# Adafruit_CC3000_Breakout.net
KiCad netlist of a schematic drawn in EAGLE
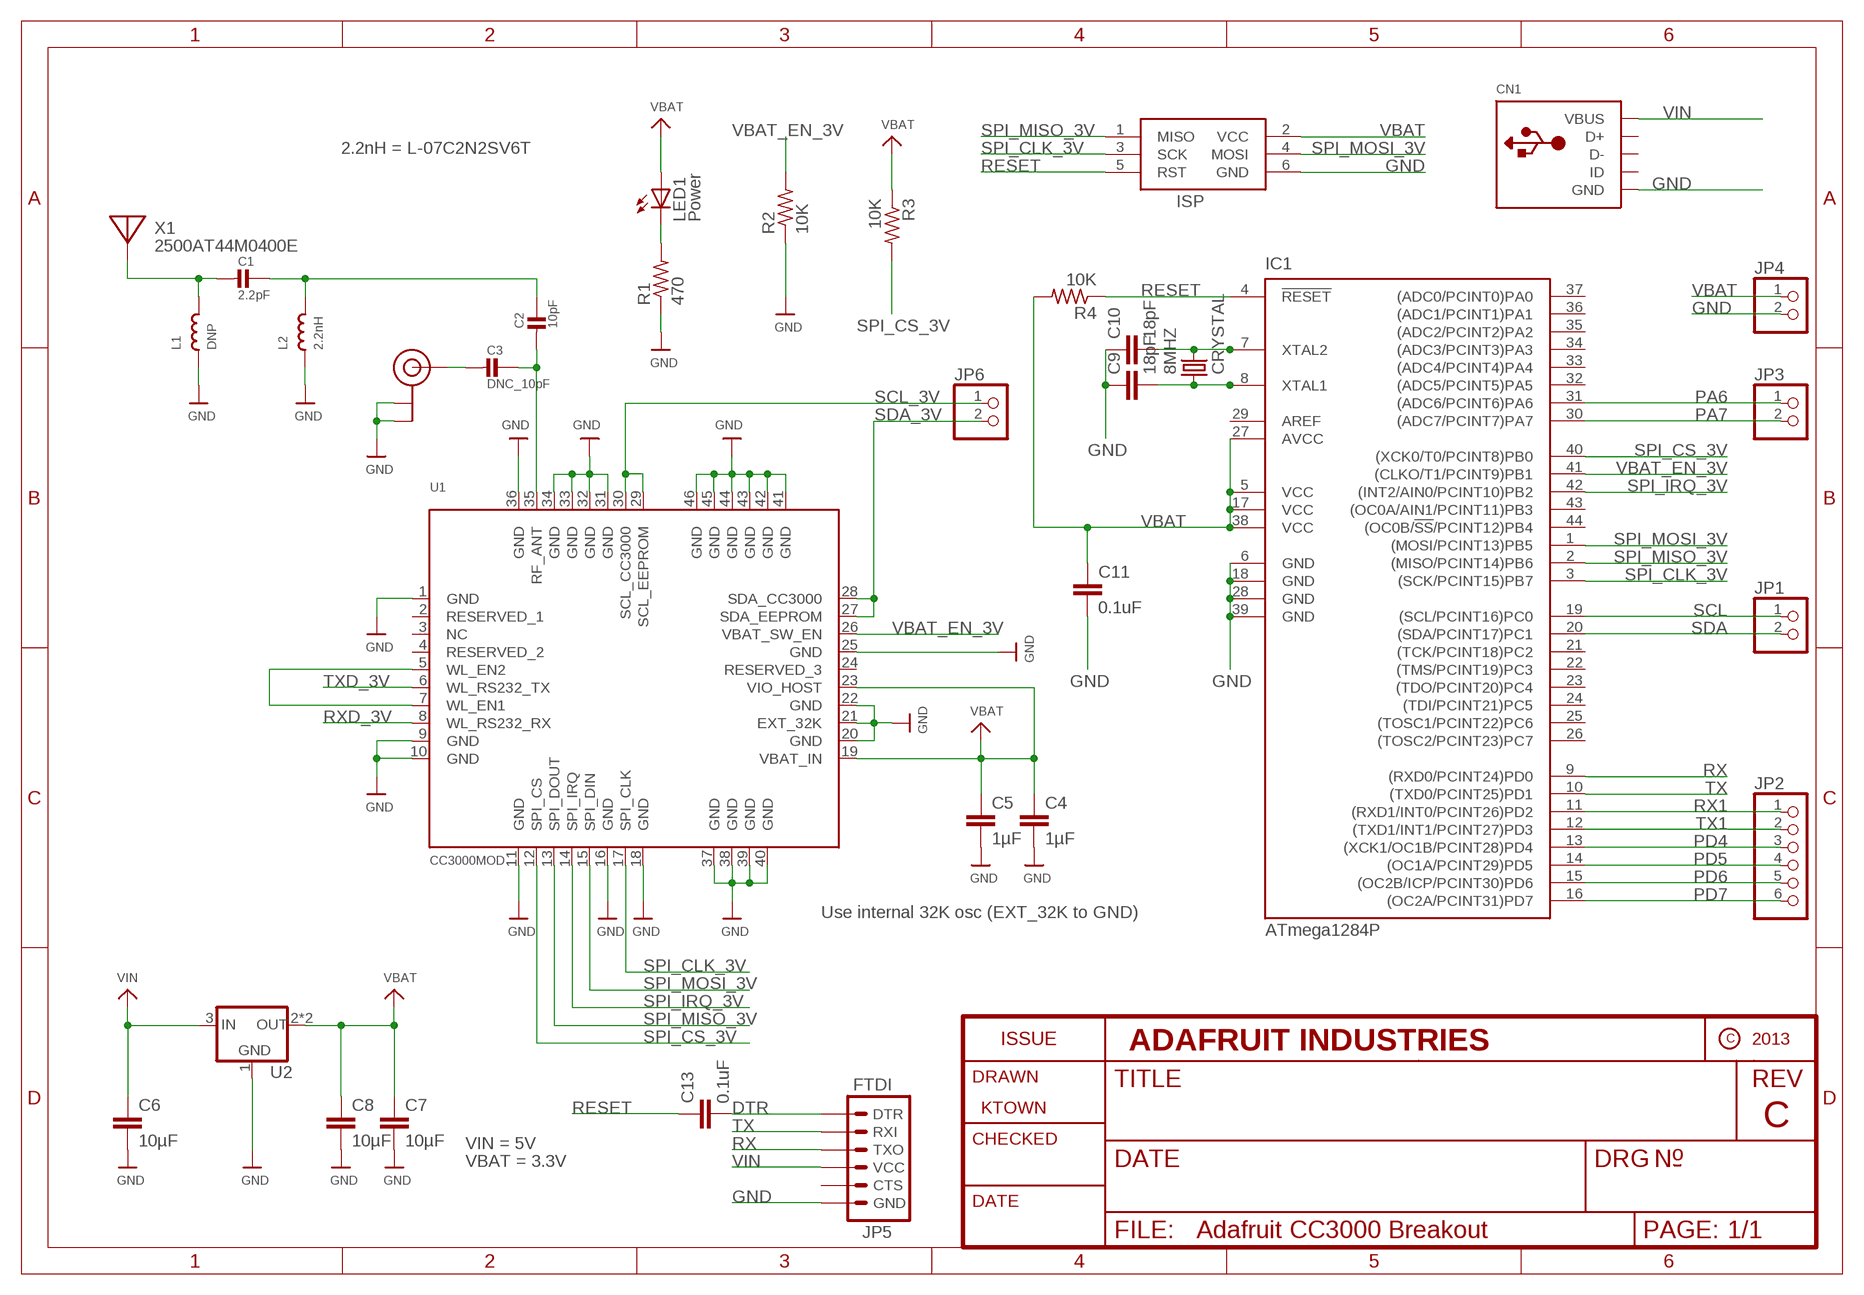
[diagram p0: schematic, sheet 1]

(export (version "E")
  (design (tool "Eeschema 10.0.6"))
  (components
    (comp (ref "8MHZ")
      (value "CRYSTAL")
      (footprint "eagle-import:2-SMD-5X3MM")
      (libsource (lib "eagle-import") (part "CRYSTAL"))
    )
    (comp (ref "C1")
      (value "2.2pF")
      (footprint "eagle-import:_0402")
      (libsource (lib "eagle-import") (part "CAP_CERAMIC_0402"))
    )
    (comp (ref "C2")
      (value "10pF")
      (footprint "eagle-import:_0402")
      (libsource (lib "eagle-import") (part "CAP_CERAMIC_0402"))
    )
    (comp (ref "C3")
      (value "DNC_10pF")
      (footprint "eagle-import:_0402")
      (libsource (lib "eagle-import") (part "CAP_CERAMIC_0402"))
    )
    (comp (ref "C4")
      (value "1µF")
      (footprint "eagle-import:C1206")
      (libsource (lib "eagle-import") (part "C-EUC1206"))
    )
    (comp (ref "C5")
      (value "1µF")
      (footprint "eagle-import:C1206")
      (libsource (lib "eagle-import") (part "C-EUC1206"))
    )
    (comp (ref "C6")
      (value "10µF")
      (footprint "eagle-import:C1206")
      (libsource (lib "eagle-import") (part "C-EUC1206"))
    )
    (comp (ref "C7")
      (value "10µF")
      (footprint "eagle-import:C1206")
      (libsource (lib "eagle-import") (part "C-EUC1206"))
    )
    (comp (ref "C8")
      (value "10µF")
      (footprint "eagle-import:C1206")
      (libsource (lib "eagle-import") (part "C-EUC1206"))
    )
    (comp (ref "C9")
      (value "18pF")
      (footprint "eagle-import:C1206")
      (libsource (lib "eagle-import") (part "C-EUC1206"))
    )
    (comp (ref "C10")
      (value "18pF")
      (footprint "eagle-import:C1206")
      (libsource (lib "eagle-import") (part "C-EUC1206"))
    )
    (comp (ref "C11")
      (value "0.1uF")
      (footprint "eagle-import:C1206")
      (libsource (lib "eagle-import") (part "C-EUC1206"))
    )
    (comp (ref "C13")
      (value "0.1uF")
      (footprint "eagle-import:C1206")
      (libsource (lib "eagle-import") (part "C-EUC1206"))
    )
    (comp (ref "CN1")
      (value "USBPWR")
      (footprint "eagle-import:USB-MINIB-POWER")
      (libsource (lib "eagle-import") (part "USBPWR"))
    )
    (comp (ref "IC1")
      (value "ATmega1284P")
      (footprint "eagle-import:TQFP44")
      (libsource (lib "eagle-import") (part "MEGA164P/324P/644P-AU"))
    )
    (comp (ref "ISP")
      (value "AVRISP-6")
      (footprint "eagle-import:AVRISP")
      (libsource (lib "eagle-import") (part "AVRISP-6"))
    )
    (comp (ref "JP1")
      (value "PINHD-1X2")
      (footprint "eagle-import:1X02")
      (libsource (lib "eagle-import") (part "PINHD-1X2"))
    )
    (comp (ref "JP2")
      (value "PINHD-1X6")
      (footprint "eagle-import:1X06")
      (libsource (lib "eagle-import") (part "PINHD-1X6"))
    )
    (comp (ref "JP3")
      (value "PINHD-1X2")
      (footprint "eagle-import:1X02")
      (libsource (lib "eagle-import") (part "PINHD-1X2"))
    )
    (comp (ref "JP4")
      (value "PINHD-1X2")
      (footprint "eagle-import:1X02")
      (libsource (lib "eagle-import") (part "PINHD-1X2"))
    )
    (comp (ref "JP5")
      (value "FTDI")
      (footprint "eagle-import:1X06")
      (libsource (lib "eagle-import") (part "ARDUINO_SERIAL_PROGRAMPTH"))
    )
    (comp (ref "JP6")
      (value "PINHD-1X2")
      (footprint "eagle-import:1X02")
      (libsource (lib "eagle-import") (part "PINHD-1X2"))
    )
    (comp (ref "L1")
      (value "DNP")
      (footprint "eagle-import:_0402")
      (libsource (lib "eagle-import") (part "INDUCTOR_0402"))
    )
    (comp (ref "L2")
      (value "2.2nH")
      (footprint "eagle-import:_0402")
      (libsource (lib "eagle-import") (part "INDUCTOR_0402"))
    )
    (comp (ref "LED1")
      (value "Power")
      (footprint "eagle-import:1206")
      (libsource (lib "eagle-import") (part "LEDSMT1206"))
    )
    (comp (ref "R1")
      (value "470")
      (footprint "eagle-import:R1206")
      (libsource (lib "eagle-import") (part "R-US_R1206"))
    )
    (comp (ref "R2")
      (value "10K")
      (footprint "eagle-import:R1206")
      (libsource (lib "eagle-import") (part "R-US_R1206"))
    )
    (comp (ref "R3")
      (value "10K")
      (footprint "eagle-import:R1206")
      (libsource (lib "eagle-import") (part "R-US_R1206"))
    )
    (comp (ref "R4")
      (value "10K")
      (footprint "eagle-import:R1206")
      (libsource (lib "eagle-import") (part "R-US_R1206"))
    )
    (comp (ref "U$35")
      (value "U.FL")
      (footprint "eagle-import:U.FL")
      (libsource (lib "eagle-import") (part "U.FL"))
    )
    (comp (ref "U1")
      (value "CC3000MOD")
      (footprint "eagle-import:CC3000MOD")
      (libsource (lib "eagle-import") (part "CC3000MOD"))
    )
    (comp (ref "U2")
      (value "VREG_SOT223")
      (footprint "eagle-import:SOT223-R")
      (libsource (lib "eagle-import") (part "VREG_SOT223"))
    )
    (comp (ref "X1")
      (value "2500AT44M0400E")
      (footprint "eagle-import:ANT_2500AT44M0400")
      (libsource (lib "eagle-import") (part "ANTENNA_JOHANSON_2500AT44M0400"))
    )
  )
  (nets
    (net (code "1") (name "/AREF") (class "Default")
      (node (ref "IC1") (pin "29") (pinfunction "AREF_29") (pintype "power_in"))
    )
    (net (code "2") (name "/DTR") (class "Default")
      (node (ref "C13") (pin "2") (pinfunction "2_2") (pintype "passive"))
      (node (ref "JP5") (pin "DTR") (pinfunction "DTR_DTR") (pintype "passive"))
    )
    (net (code "3") (name "/PA6") (class "Default")
      (node (ref "IC1") (pin "31") (pinfunction "(ADC6/PCINT6)PA6_31") (pintype "bidirectional"))
      (node (ref "JP3") (pin "1") (pinfunction "1_1") (pintype "passive"))
    )
    (net (code "4") (name "/PA7") (class "Default")
      (node (ref "IC1") (pin "30") (pinfunction "(ADC7/PCINT7)PA7_30") (pintype "bidirectional"))
      (node (ref "JP3") (pin "2") (pinfunction "2_2") (pintype "passive"))
    )
    (net (code "5") (name "/PD4") (class "Default")
      (node (ref "IC1") (pin "13") (pinfunction "(XCK1/OC1B/PCINT28)PD4_13") (pintype "bidirectional"))
      (node (ref "JP2") (pin "3") (pinfunction "3_3") (pintype "passive"))
    )
    (net (code "6") (name "/PD5") (class "Default")
      (node (ref "IC1") (pin "14") (pinfunction "(OC1A/PCINT29)PD5_14") (pintype "bidirectional"))
      (node (ref "JP2") (pin "4") (pinfunction "4_4") (pintype "passive"))
    )
    (net (code "7") (name "/PD6") (class "Default")
      (node (ref "IC1") (pin "15") (pinfunction "(OC2B/ICP/PCINT30)PD6_15") (pintype "bidirectional"))
      (node (ref "JP2") (pin "5") (pinfunction "5_5") (pintype "passive"))
    )
    (net (code "8") (name "/PD7") (class "Default")
      (node (ref "IC1") (pin "16") (pinfunction "(OC2A/PCINT31)PD7_16") (pintype "bidirectional"))
      (node (ref "JP2") (pin "6") (pinfunction "6_6") (pintype "passive"))
    )
    (net (code "9") (name "/RESET") (class "Default")
      (node (ref "C13") (pin "1") (pinfunction "1_1") (pintype "passive"))
      (node (ref "IC1") (pin "4") (pinfunction "~{RESET}_4") (pintype "input"))
      (node (ref "ISP") (pin "5") (pinfunction "RST_5") (pintype "output"))
      (node (ref "R4") (pin "1") (pinfunction "1_1") (pintype "passive"))
    )
    (net (code "10") (name "/RX") (class "Default")
      (node (ref "IC1") (pin "9") (pinfunction "(RXD0/PCINT24)PD0_9") (pintype "bidirectional"))
      (node (ref "JP5") (pin "TXO") (pinfunction "TXO_TXO") (pintype "passive"))
    )
    (net (code "11") (name "/RX1") (class "Default")
      (node (ref "IC1") (pin "11") (pinfunction "(RXD1/INT0/PCINT26)PD2_11") (pintype "bidirectional"))
      (node (ref "JP2") (pin "1") (pinfunction "1_1") (pintype "passive"))
    )
    (net (code "12") (name "/RXD_3V") (class "Default")
      (node (ref "U1") (pin "8") (pinfunction "WL_RS232_RX_8") (pintype "input"))
    )
    (net (code "13") (name "/SCL") (class "Default")
      (node (ref "IC1") (pin "19") (pinfunction "(SCL/PCINT16)PC0_19") (pintype "bidirectional"))
      (node (ref "JP1") (pin "1") (pinfunction "1_1") (pintype "passive"))
    )
    (net (code "14") (name "/SCL_3V") (class "Default")
      (node (ref "JP6") (pin "1") (pinfunction "1_1") (pintype "passive"))
      (node (ref "U1") (pin "29") (pinfunction "SCL_EEPROM_29") (pintype "bidirectional"))
      (node (ref "U1") (pin "30") (pinfunction "SCL_CC3000_30") (pintype "bidirectional"))
    )
    (net (code "15") (name "/SDA") (class "Default")
      (node (ref "IC1") (pin "20") (pinfunction "(SDA/PCINT17)PC1_20") (pintype "bidirectional"))
      (node (ref "JP1") (pin "2") (pinfunction "2_2") (pintype "passive"))
    )
    (net (code "16") (name "/SDA_3V") (class "Default")
      (node (ref "JP6") (pin "2") (pinfunction "2_2") (pintype "passive"))
      (node (ref "U1") (pin "27") (pinfunction "SDA_EEPROM_27") (pintype "bidirectional"))
      (node (ref "U1") (pin "28") (pinfunction "SDA_CC3000_28") (pintype "bidirectional"))
    )
    (net (code "17") (name "/SPI_CLK_3V") (class "Default")
      (node (ref "IC1") (pin "3") (pinfunction "(SCK/PCINT15)PB7_3") (pintype "bidirectional"))
      (node (ref "ISP") (pin "3") (pinfunction "SCK_3") (pintype "output"))
      (node (ref "U1") (pin "17") (pinfunction "SPI_CLK_17") (pintype "input"))
    )
    (net (code "18") (name "/SPI_CS_3V") (class "Default")
      (node (ref "IC1") (pin "40") (pinfunction "(XCK0/T0/PCINT8)PB0_40") (pintype "bidirectional"))
      (node (ref "R3") (pin "2") (pinfunction "2_2") (pintype "passive"))
      (node (ref "U1") (pin "12") (pinfunction "SPI_CS_12") (pintype "input"))
    )
    (net (code "19") (name "/SPI_IRQ_3V") (class "Default")
      (node (ref "IC1") (pin "42") (pinfunction "(INT2/AIN0/PCINT10)PB2_42") (pintype "bidirectional"))
      (node (ref "U1") (pin "14") (pinfunction "SPI_IRQ_14") (pintype "output"))
    )
    (net (code "20") (name "/SPI_MISO_3V") (class "Default")
      (node (ref "IC1") (pin "2") (pinfunction "(MISO/PCINT14)PB6_2") (pintype "bidirectional"))
      (node (ref "ISP") (pin "1") (pinfunction "MISO_1") (pintype "input"))
      (node (ref "U1") (pin "13") (pinfunction "SPI_DOUT_13") (pintype "output"))
    )
    (net (code "21") (name "/SPI_MOSI_3V") (class "Default")
      (node (ref "IC1") (pin "1") (pinfunction "(MOSI/PCINT13)PB5_1") (pintype "bidirectional"))
      (node (ref "ISP") (pin "4") (pinfunction "MOSI_4") (pintype "output"))
      (node (ref "U1") (pin "15") (pinfunction "SPI_DIN_15") (pintype "input"))
    )
    (net (code "22") (name "/TX") (class "Default")
      (node (ref "IC1") (pin "10") (pinfunction "(TXD0/PCINT25)PD1_10") (pintype "bidirectional"))
      (node (ref "JP5") (pin "RXI") (pinfunction "RXI_RXI") (pintype "passive"))
    )
    (net (code "23") (name "/TX1") (class "Default")
      (node (ref "IC1") (pin "12") (pinfunction "(TXD1/INT1/PCINT27)PD3_12") (pintype "bidirectional"))
      (node (ref "JP2") (pin "2") (pinfunction "2_2") (pintype "passive"))
    )
    (net (code "24") (name "/TXD_3V") (class "Default")
      (node (ref "U1") (pin "6") (pinfunction "WL_RS232_TX_6") (pintype "output"))
    )
    (net (code "25") (name "/VBAT_EN_3V") (class "Default")
      (node (ref "IC1") (pin "41") (pinfunction "(CLKO/T1/PCINT9)PB1_41") (pintype "bidirectional"))
      (node (ref "R2") (pin "2") (pinfunction "2_2") (pintype "passive"))
      (node (ref "U1") (pin "26") (pinfunction "VBAT_SW_EN_26") (pintype "input"))
    )
    (net (code "26") (name "GND") (class "Default")
      (node (ref "C10") (pin "1") (pinfunction "1_1") (pintype "passive"))
      (node (ref "C11") (pin "2") (pinfunction "2_2") (pintype "passive"))
      (node (ref "C4") (pin "2") (pinfunction "2_2") (pintype "passive"))
      (node (ref "C5") (pin "2") (pinfunction "2_2") (pintype "passive"))
      (node (ref "C6") (pin "2") (pinfunction "2_2") (pintype "passive"))
      (node (ref "C7") (pin "2") (pinfunction "2_2") (pintype "passive"))
      (node (ref "C8") (pin "2") (pinfunction "2_2") (pintype "passive"))
      (node (ref "C9") (pin "1") (pinfunction "1_1") (pintype "passive"))
      (node (ref "CN1") (pin "GND") (pinfunction "GND_GND") (pintype "power_in"))
      (node (ref "IC1") (pin "18") (pinfunction "GND_18") (pintype "power_in"))
      (node (ref "IC1") (pin "28") (pinfunction "GND_28") (pintype "power_in"))
      (node (ref "IC1") (pin "39") (pinfunction "GND_39") (pintype "power_in"))
      (node (ref "IC1") (pin "6") (pinfunction "GND_6") (pintype "power_in"))
      (node (ref "ISP") (pin "6") (pinfunction "GND_6") (pintype "power_in"))
      (node (ref "JP4") (pin "2") (pinfunction "2_2") (pintype "passive"))
      (node (ref "JP5") (pin "GND") (pinfunction "GND_GND") (pintype "passive"))
      (node (ref "L1") (pin "1") (pinfunction "1_1") (pintype "passive"))
      (node (ref "L2") (pin "1") (pinfunction "1_1") (pintype "passive"))
      (node (ref "R1") (pin "1") (pinfunction "1_1") (pintype "passive"))
      (node (ref "R2") (pin "1") (pinfunction "1_1") (pintype "passive"))
      (node (ref "U$35") (pin "P$1") (pinfunction "GND_P$1") (pintype "bidirectional"))
      (node (ref "U$35") (pin "P$2") (pinfunction "GND_P$2") (pintype "bidirectional"))
      (node (ref "U1") (pin "1") (pinfunction "GND_1") (pintype "power_in"))
      (node (ref "U1") (pin "10") (pinfunction "GND_10") (pintype "power_in"))
      (node (ref "U1") (pin "11") (pinfunction "GND_11") (pintype "power_in"))
      (node (ref "U1") (pin "16") (pinfunction "GND_16") (pintype "power_in"))
      (node (ref "U1") (pin "18") (pinfunction "GND_18") (pintype "power_in"))
      (node (ref "U1") (pin "20") (pinfunction "GND_20") (pintype "power_in"))
      (node (ref "U1") (pin "21") (pinfunction "EXT_32K_21") (pintype "bidirectional"))
      (node (ref "U1") (pin "22") (pinfunction "GND_22") (pintype "power_in"))
      (node (ref "U1") (pin "25") (pinfunction "GND_25") (pintype "power_in"))
      (node (ref "U1") (pin "31") (pinfunction "GND_31") (pintype "power_in"))
      (node (ref "U1") (pin "32") (pinfunction "GND_32") (pintype "power_in"))
      (node (ref "U1") (pin "33") (pinfunction "GND_33") (pintype "power_in"))
      (node (ref "U1") (pin "34") (pinfunction "GND_34") (pintype "power_in"))
      (node (ref "U1") (pin "36") (pinfunction "GND_36") (pintype "power_in"))
      (node (ref "U1") (pin "37") (pinfunction "GND_37") (pintype "power_in"))
      (node (ref "U1") (pin "38") (pinfunction "GND_38") (pintype "power_in"))
      (node (ref "U1") (pin "39") (pinfunction "GND_39") (pintype "power_in"))
      (node (ref "U1") (pin "40") (pinfunction "GND_40") (pintype "power_in"))
      (node (ref "U1") (pin "41") (pinfunction "GND_41") (pintype "power_in"))
      (node (ref "U1") (pin "42") (pinfunction "GND_42") (pintype "power_in"))
      (node (ref "U1") (pin "43") (pinfunction "GND_43") (pintype "power_in"))
      (node (ref "U1") (pin "44") (pinfunction "GND_44") (pintype "power_in"))
      (node (ref "U1") (pin "45") (pinfunction "GND_45") (pintype "power_in"))
      (node (ref "U1") (pin "46") (pinfunction "GND_46") (pintype "power_in"))
      (node (ref "U1") (pin "9") (pinfunction "GND_9") (pintype "power_in"))
      (node (ref "U2") (pin "1") (pinfunction "GND_1") (pintype "power_in"))
    )
    (net (code "27") (name "Net-(8MHZ-1)") (class "Default")
      (node (ref "8MHZ") (pin "P$1") (pinfunction "1_P$1") (pintype "passive"))
      (node (ref "C9") (pin "2") (pinfunction "2_2") (pintype "passive"))
      (node (ref "IC1") (pin "8") (pinfunction "XTAL1_8") (pintype "input"))
    )
    (net (code "28") (name "Net-(8MHZ-2)") (class "Default")
      (node (ref "8MHZ") (pin "P$2") (pinfunction "2_P$2") (pintype "passive"))
      (node (ref "C10") (pin "2") (pinfunction "2_2") (pintype "passive"))
      (node (ref "IC1") (pin "7") (pinfunction "XTAL2_7") (pintype "output"))
    )
    (net (code "29") (name "Net-(C1-Pad1)") (class "Default")
      (node (ref "C1") (pin "1") (pinfunction "1_1") (pintype "passive"))
      (node (ref "C2") (pin "1") (pinfunction "1_1") (pintype "passive"))
      (node (ref "L2") (pin "2") (pinfunction "2_2") (pintype "passive"))
    )
    (net (code "30") (name "Net-(LED1-PadC)") (class "Default")
      (node (ref "LED1") (pin "C") (pinfunction "C_C") (pintype "passive"))
      (node (ref "R1") (pin "2") (pinfunction "2_2") (pintype "passive"))
    )
    (net (code "31") (name "Net-(U$35-SIGNAL)") (class "Default")
      (node (ref "C3") (pin "2") (pinfunction "2_2") (pintype "passive"))
      (node (ref "U$35") (pin "P$3") (pinfunction "SIGNAL_P$3") (pintype "bidirectional"))
    )
    (net (code "32") (name "Net-(U1-RF_ANT)") (class "Default")
      (node (ref "C2") (pin "2") (pinfunction "2_2") (pintype "passive"))
      (node (ref "C3") (pin "1") (pinfunction "1_1") (pintype "passive"))
      (node (ref "U1") (pin "35") (pinfunction "RF_ANT_35") (pintype "bidirectional"))
    )
    (net (code "33") (name "Net-(U1-WL_EN1)") (class "Default")
      (node (ref "U1") (pin "5") (pinfunction "WL_EN2_5") (pintype "input"))
      (node (ref "U1") (pin "7") (pinfunction "WL_EN1_7") (pintype "input"))
    )
    (net (code "34") (name "Net-(X1-P$1)") (class "Default")
      (node (ref "C1") (pin "2") (pinfunction "2_2") (pintype "passive"))
      (node (ref "L1") (pin "2") (pinfunction "2_2") (pintype "passive"))
      (node (ref "X1") (pin "FEED") (pinfunction "P$1_FEED") (pintype "passive"))
    )
    (net (code "35") (name "VBAT") (class "Default")
      (node (ref "C11") (pin "1") (pinfunction "1_1") (pintype "passive"))
      (node (ref "C4") (pin "1") (pinfunction "1_1") (pintype "passive"))
      (node (ref "C5") (pin "1") (pinfunction "1_1") (pintype "passive"))
      (node (ref "C7") (pin "1") (pinfunction "1_1") (pintype "passive"))
      (node (ref "C8") (pin "1") (pinfunction "1_1") (pintype "passive"))
      (node (ref "IC1") (pin "17") (pinfunction "VCC_17") (pintype "power_in"))
      (node (ref "IC1") (pin "27") (pinfunction "AVCC_27") (pintype "power_in"))
      (node (ref "IC1") (pin "38") (pinfunction "VCC_38") (pintype "power_in"))
      (node (ref "IC1") (pin "5") (pinfunction "VCC_5") (pintype "power_in"))
      (node (ref "ISP") (pin "2") (pinfunction "VCC_2") (pintype "power_in"))
      (node (ref "JP4") (pin "1") (pinfunction "1_1") (pintype "passive"))
      (node (ref "LED1") (pin "A") (pinfunction "A_A") (pintype "passive"))
      (node (ref "R3") (pin "1") (pinfunction "1_1") (pintype "passive"))
      (node (ref "R4") (pin "2") (pinfunction "2_2") (pintype "passive"))
      (node (ref "U1") (pin "19") (pinfunction "VBAT_IN_19") (pintype "power_in"))
      (node (ref "U1") (pin "23") (pinfunction "VIO_HOST_23") (pintype "power_in"))
      (node (ref "U2") (pin "2") (pinfunction "OUT_2") (pintype "power_in"))
      (node (ref "U2") (pin "4") (pinfunction "OUT_4") (pintype "power_in"))
    )
    (net (code "36") (name "VIN") (class "Default")
      (node (ref "C6") (pin "1") (pinfunction "1_1") (pintype "passive"))
      (node (ref "CN1") (pin "VBUS") (pinfunction "VBUS_VBUS") (pintype "power_in"))
      (node (ref "JP5") (pin "VCC") (pinfunction "VCC_VCC") (pintype "passive"))
      (node (ref "U2") (pin "3") (pinfunction "IN_3") (pintype "power_in"))
    )
    (net (code "37") (name "unconnected-(CN1-PadD+)") (class "Default")
      (node (ref "CN1") (pin "D+") (pinfunction "D+_D+") (pintype "bidirectional"))
    )
    (net (code "38") (name "unconnected-(CN1-PadD-)") (class "Default")
      (node (ref "CN1") (pin "D-") (pinfunction "D-_D-") (pintype "bidirectional"))
    )
    (net (code "39") (name "unconnected-(CN1-PadID)") (class "Default")
      (node (ref "CN1") (pin "ID") (pinfunction "ID_ID") (pintype "bidirectional"))
    )
    (net (code "40") (name "unconnected-(IC1-(ADC0{slash}PCINT0)PA0-Pad37)") (class "Default")
      (node (ref "IC1") (pin "37") (pinfunction "(ADC0/PCINT0)PA0_37") (pintype "bidirectional"))
    )
    (net (code "41") (name "unconnected-(IC1-(ADC1{slash}PCINT1)PA1-Pad36)") (class "Default")
      (node (ref "IC1") (pin "36") (pinfunction "(ADC1/PCINT1)PA1_36") (pintype "bidirectional"))
    )
    (net (code "42") (name "unconnected-(IC1-(ADC2{slash}PCINT2)PA2-Pad35)") (class "Default")
      (node (ref "IC1") (pin "35") (pinfunction "(ADC2/PCINT2)PA2_35") (pintype "bidirectional"))
    )
    (net (code "43") (name "unconnected-(IC1-(ADC3{slash}PCINT3)PA3-Pad34)") (class "Default")
      (node (ref "IC1") (pin "34") (pinfunction "(ADC3/PCINT3)PA3_34") (pintype "bidirectional"))
    )
    (net (code "44") (name "unconnected-(IC1-(ADC4{slash}PCINT4)PA4-Pad33)") (class "Default")
      (node (ref "IC1") (pin "33") (pinfunction "(ADC4/PCINT4)PA4_33") (pintype "bidirectional"))
    )
    (net (code "45") (name "unconnected-(IC1-(ADC5{slash}PCINT5)PA5-Pad32)") (class "Default")
      (node (ref "IC1") (pin "32") (pinfunction "(ADC5/PCINT5)PA5_32") (pintype "bidirectional"))
    )
    (net (code "46") (name "unconnected-(IC1-(OC0A{slash}AIN1{slash}PCINT11)PB3-Pad43)") (class "Default")
      (node (ref "IC1") (pin "43") (pinfunction "(OC0A/AIN1/PCINT11)PB3_43") (pintype "bidirectional"))
    )
    (net (code "47") (name "unconnected-(IC1-(OC0B{slash}~{SS}{slash}PCINT12)PB4-Pad44)") (class "Default")
      (node (ref "IC1") (pin "44") (pinfunction "(OC0B/~{SS}/PCINT12)PB4_44") (pintype "bidirectional"))
    )
    (net (code "48") (name "unconnected-(IC1-(TCK{slash}PCINT18)PC2-Pad21)") (class "Default")
      (node (ref "IC1") (pin "21") (pinfunction "(TCK/PCINT18)PC2_21") (pintype "bidirectional"))
    )
    (net (code "49") (name "unconnected-(IC1-(TDI{slash}PCINT21)PC5-Pad24)") (class "Default")
      (node (ref "IC1") (pin "24") (pinfunction "(TDI/PCINT21)PC5_24") (pintype "bidirectional"))
    )
    (net (code "50") (name "unconnected-(IC1-(TDO{slash}PCINT20)PC4-Pad23)") (class "Default")
      (node (ref "IC1") (pin "23") (pinfunction "(TDO/PCINT20)PC4_23") (pintype "bidirectional"))
    )
    (net (code "51") (name "unconnected-(IC1-(TMS{slash}PCINT19)PC3-Pad22)") (class "Default")
      (node (ref "IC1") (pin "22") (pinfunction "(TMS/PCINT19)PC3_22") (pintype "bidirectional"))
    )
    (net (code "52") (name "unconnected-(IC1-(TOSC1{slash}PCINT22)PC6-Pad25)") (class "Default")
      (node (ref "IC1") (pin "25") (pinfunction "(TOSC1/PCINT22)PC6_25") (pintype "bidirectional"))
    )
    (net (code "53") (name "unconnected-(IC1-(TOSC2{slash}PCINT23)PC7-Pad26)") (class "Default")
      (node (ref "IC1") (pin "26") (pinfunction "(TOSC2/PCINT23)PC7_26") (pintype "bidirectional"))
    )
    (net (code "54") (name "unconnected-(JP5-PadCTS)") (class "Default")
      (node (ref "JP5") (pin "CTS") (pinfunction "CTS_CTS") (pintype "passive"))
    )
    (net (code "55") (name "unconnected-(U1-NC-Pad3)") (class "Default")
      (node (ref "U1") (pin "3") (pinfunction "NC_3") (pintype "no_connect"))
    )
    (net (code "56") (name "unconnected-(U1-RESERVED_1-Pad2)") (class "Default")
      (node (ref "U1") (pin "2") (pinfunction "RESERVED_1_2") (pintype "bidirectional"))
    )
    (net (code "57") (name "unconnected-(U1-RESERVED_2-Pad4)") (class "Default")
      (node (ref "U1") (pin "4") (pinfunction "RESERVED_2_4") (pintype "bidirectional"))
    )
    (net (code "58") (name "unconnected-(U1-RESERVED_3-Pad24)") (class "Default")
      (node (ref "U1") (pin "24") (pinfunction "RESERVED_3_24") (pintype "bidirectional"))
    )
  )
)
